# v1.net
KiCad netlist of a schematic drawn in EAGLE
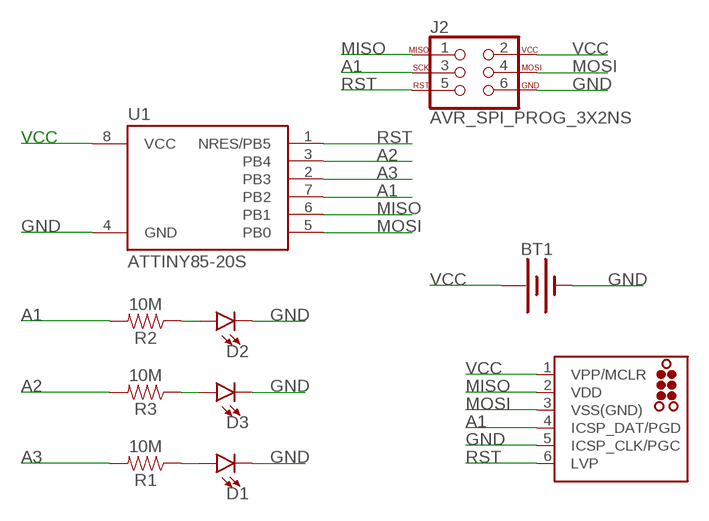
[diagram p0: schematic, sheet 1]

(export (version "E")
  (design (tool "Eeschema 10.0.6"))
  (components
    (comp (ref "BT1")
      (value "BATTERY-20MM_SMD")
      (footprint "eagle-import:BATTCON_20MM")
      (libsource (lib "eagle-import") (part "BATTERY-20MM_SMD"))
    )
    (comp (ref "D1")
      (value "LED5MM")
      (footprint "eagle-import:LED_5MM")
      (libsource (lib "eagle-import") (part "LED5MM"))
    )
    (comp (ref "D2")
      (value "LED5MM")
      (footprint "eagle-import:LED_5MM")
      (libsource (lib "eagle-import") (part "LED5MM"))
    )
    (comp (ref "D3")
      (value "LED5MM")
      (footprint "eagle-import:LED_5MM")
      (libsource (lib "eagle-import") (part "LED5MM"))
    )
    (comp (ref "J1")
      (value "TC2030-MCP-NL")
      (footprint "eagle-import:TC2030-MCP-NL")
      (libsource (lib "eagle-import") (part "TC2030-MCP-NL"))
    )
    (comp (ref "J2")
      (value "AVR_SPI_PROG_3X2NS")
      (footprint "eagle-import:2X3-NS")
      (libsource (lib "eagle-import") (part "AVR_SPI_PROG_3X2NS"))
    )
    (comp (ref "R1")
      (value "10M")
      (footprint "eagle-import:AXIAL-0.3")
      (libsource (lib "eagle-import") (part "10MOHM-HORIZ-1/4W-5%"))
    )
    (comp (ref "R2")
      (value "10M")
      (footprint "eagle-import:AXIAL-0.3")
      (libsource (lib "eagle-import") (part "10MOHM-HORIZ-1/4W-5%"))
    )
    (comp (ref "R3")
      (value "10M")
      (footprint "eagle-import:AXIAL-0.3")
      (libsource (lib "eagle-import") (part "10MOHM-HORIZ-1/4W-5%"))
    )
    (comp (ref "U1")
      (value "ATTINY85-20S")
      (footprint "eagle-import:SOIC8_EIAJ_208MIL")
      (libsource (lib "eagle-import") (part "ATTINY85S-20"))
    )
  )
  (nets
    (net (code "1") (name "/A1") (class "Default")
      (node (ref "J1") (pin "4") (pinfunction "ICSP_DAT/PGD_4") (pintype "bidirectional"))
      (node (ref "J2") (pin "3") (pinfunction "3_3") (pintype "passive"))
      (node (ref "R2") (pin "P$2") (pinfunction "2_P$2") (pintype "passive"))
      (node (ref "U1") (pin "7") (pinfunction "PB2_7") (pintype "bidirectional"))
    )
    (net (code "2") (name "/A2") (class "Default")
      (node (ref "R3") (pin "P$2") (pinfunction "2_P$2") (pintype "passive"))
      (node (ref "U1") (pin "3") (pinfunction "PB4_3") (pintype "bidirectional"))
    )
    (net (code "3") (name "/A3") (class "Default")
      (node (ref "R1") (pin "P$2") (pinfunction "2_P$2") (pintype "passive"))
      (node (ref "U1") (pin "2") (pinfunction "PB3_2") (pintype "bidirectional"))
    )
    (net (code "4") (name "/GND") (class "Default")
      (node (ref "BT1") (pin "2") (pinfunction "-_2") (pintype "power_in"))
      (node (ref "D1") (pin "K") (pinfunction "C_K") (pintype "passive"))
      (node (ref "D2") (pin "K") (pinfunction "C_K") (pintype "passive"))
      (node (ref "D3") (pin "K") (pinfunction "C_K") (pintype "passive"))
      (node (ref "J1") (pin "5") (pinfunction "ICSP_CLK/PGC_5") (pintype "output"))
      (node (ref "J2") (pin "6") (pinfunction "6_6") (pintype "passive"))
      (node (ref "U1") (pin "4") (pinfunction "GND_4") (pintype "power_in"))
    )
    (net (code "5") (name "/MISO") (class "Default")
      (node (ref "J1") (pin "2") (pinfunction "VDD_2") (pintype "power_in"))
      (node (ref "J2") (pin "1") (pinfunction "1_1") (pintype "passive"))
      (node (ref "U1") (pin "6") (pinfunction "PB1_6") (pintype "bidirectional"))
    )
    (net (code "6") (name "/MOSI") (class "Default")
      (node (ref "J1") (pin "3") (pinfunction "VSS(GND)_3") (pintype "power_in"))
      (node (ref "J2") (pin "4") (pinfunction "4_4") (pintype "passive"))
      (node (ref "U1") (pin "5") (pinfunction "PB0_5") (pintype "bidirectional"))
    )
    (net (code "7") (name "/RST") (class "Default")
      (node (ref "J1") (pin "6") (pinfunction "LVP_6") (pintype "bidirectional"))
      (node (ref "J2") (pin "5") (pinfunction "5_5") (pintype "passive"))
      (node (ref "U1") (pin "1") (pinfunction "NRES/PB5_1") (pintype "bidirectional"))
    )
    (net (code "8") (name "/VCC") (class "Default")
      (node (ref "BT1") (pin "1") (pinfunction "+_1") (pintype "power_in"))
      (node (ref "J1") (pin "1") (pinfunction "VPP/MCLR_1") (pintype "passive"))
      (node (ref "J2") (pin "2") (pinfunction "2_2") (pintype "passive"))
      (node (ref "U1") (pin "8") (pinfunction "VCC_8") (pintype "power_in"))
    )
    (net (code "9") (name "Net-(R1-1)") (class "Default")
      (node (ref "D1") (pin "A") (pinfunction "A_A") (pintype "passive"))
      (node (ref "R1") (pin "P$1") (pinfunction "1_P$1") (pintype "passive"))
    )
    (net (code "10") (name "Net-(R2-1)") (class "Default")
      (node (ref "D2") (pin "A") (pinfunction "A_A") (pintype "passive"))
      (node (ref "R2") (pin "P$1") (pinfunction "1_P$1") (pintype "passive"))
    )
    (net (code "11") (name "Net-(R3-1)") (class "Default")
      (node (ref "D3") (pin "A") (pinfunction "A_A") (pintype "passive"))
      (node (ref "R3") (pin "P$1") (pinfunction "1_P$1") (pintype "passive"))
    )
  )
)
